# Esquematico.net
KiCad netlist of a schematic drawn in Altium Designer
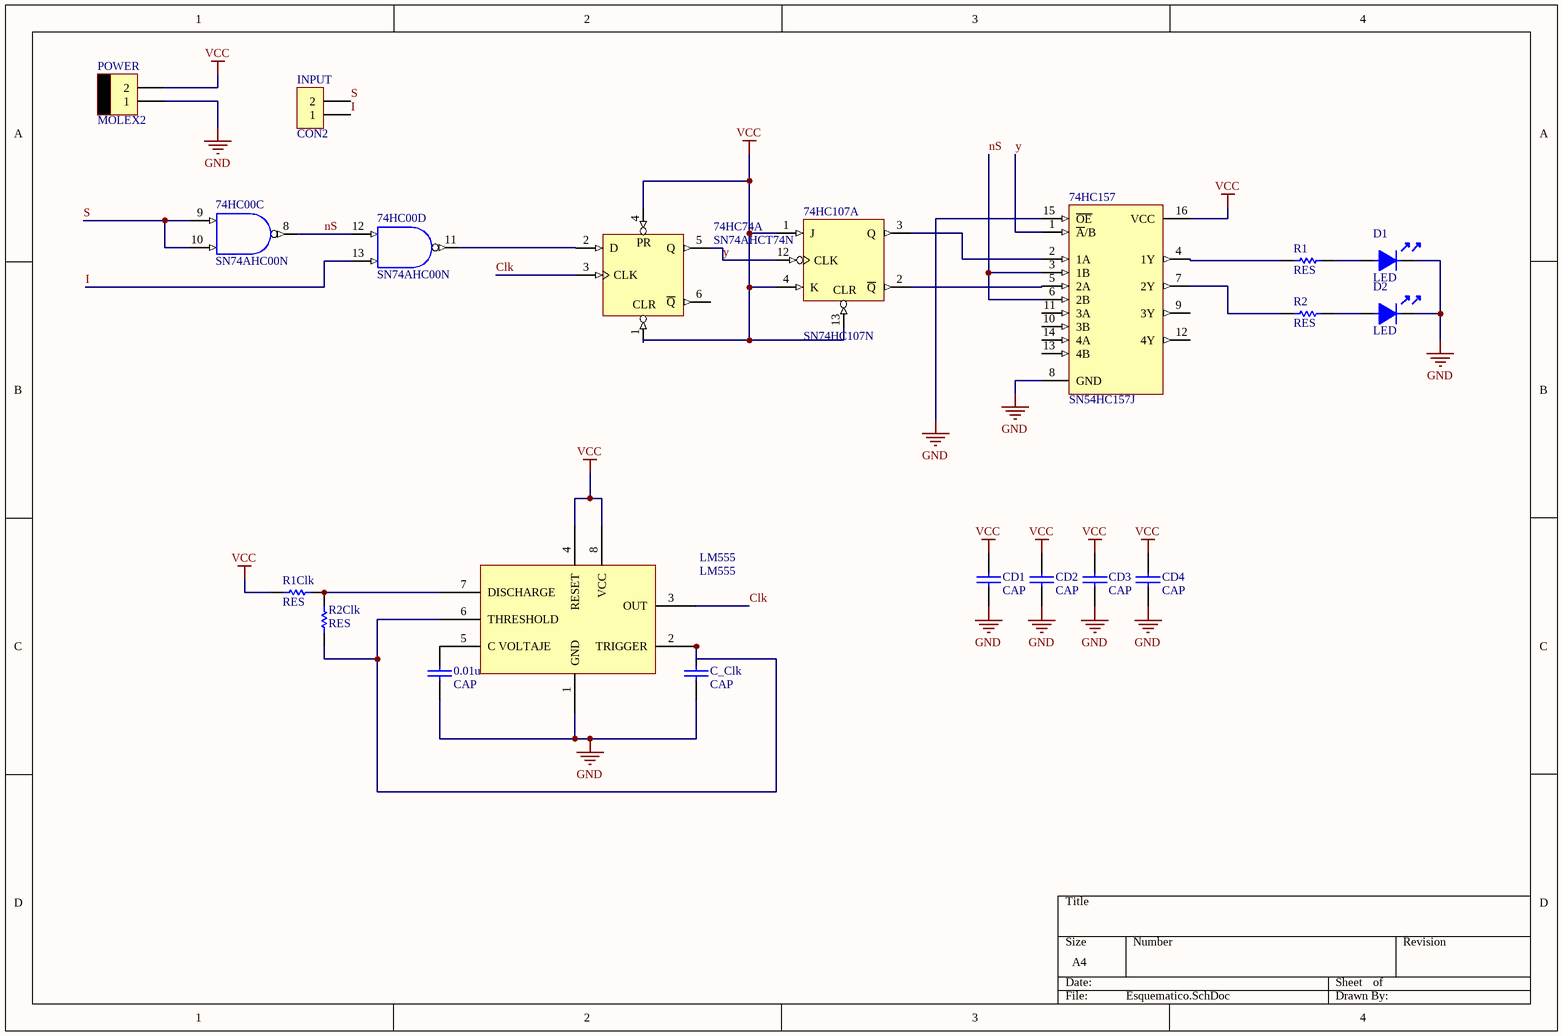
[diagram p0: Esquematico.SchDoc]

(export (version "E")
  (design (tool "Eeschema 10.0.6"))
  (components
    (comp (ref "0.01u") (value "CAP") (footprint "CAP200") (libsource (lib "LIBEBAL") (part "CAP")))
    (comp (ref "74HC00")
      (value "SN74AHC00N")
      (footprint "N014")
      (description "Quadruple 2-Input Positive-NAND Gate")
      (fields (field (name "PUBLISHER") "Altium Limited"))
      (libsource (lib "TI Logic Gate 1") (part "SN74AHC00N"))
    )
    (comp (ref "74HC74")
      (value "SN74AHCT74N")
      (footprint "N014")
      (description "Dual Positive-Edge-Triggered D-Type Flip-Flop with Clear and Preset")
      (fields (field (name "PUBLISHER") "Altium Limited"))
      (libsource (lib "TI Logic Flip-Flop") (part "SN74AHCT74N"))
    )
    (comp (ref "74HC107")
      (value "SN74HC107N")
      (footprint "N014D")
      (description "Dual J-K Negative-Edge-Triggered Flip-Flop with Clear")
      (fields (field (name "PUBLISHER") "Altium Limited"))
      (libsource (lib "TI Logic Flip-Flop") (part "SN74HC107N"))
    )
    (comp (ref "74HC157")
      (value "SN54HC157J")
      (footprint "J016")
      (description "Quadraple 2-Line to 1-Line Data Selector/Multiplexer")
      (fields (field (name "PUBLISHER") "Altium Limited"))
      (libsource (lib "TI Logic Multiplexer") (part "SN54HC157J"))
    )
    (comp (ref "CD1") (value "CAP") (footprint "CAP200") (libsource (lib "LIBEBAL") (part "CAP")))
    (comp (ref "CD2") (value "CAP") (footprint "CAP200") (libsource (lib "LIBEBAL") (part "CAP")))
    (comp (ref "CD3") (value "CAP") (footprint "CAP200") (libsource (lib "LIBEBAL") (part "CAP")))
    (comp (ref "CD4") (value "CAP") (footprint "CAP200") (libsource (lib "LIBEBAL") (part "CAP")))
    (comp (ref "C_Clk") (value "CAP") (footprint "CAP200") (libsource (lib "LIBEBAL") (part "CAP")))
    (comp (ref "D1") (value "LED") (footprint "LED3") (libsource (lib "LIBEBAL") (part "LED")))
    (comp (ref "D2") (value "LED") (footprint "LED3") (libsource (lib "LIBEBAL") (part "LED")))
    (comp (ref "INPUT") (value "CON2") (footprint "SIP2") (libsource (lib "LIBEBAL") (part "CON2")))
    (comp (ref "LM555")
      (value "LM555")
      (footprint "DIP8")
      (description "Timer")
      (libsource (lib "LIBEBAL") (part "LM555"))
    )
    (comp (ref "POWER") (value "MOLEX2") (footprint "MOLEX2") (libsource (lib "LIBEBAL") (part "MOLEX2")))
    (comp (ref "R1") (value "RES") (footprint "RES400") (libsource (lib "LIBEBAL") (part "RES")))
    (comp (ref "R1Clk") (value "RES") (footprint "RES400") (libsource (lib "LIBEBAL") (part "RES")))
    (comp (ref "R2") (value "RES") (footprint "RES400") (libsource (lib "LIBEBAL") (part "RES")))
    (comp (ref "R2Clk") (value "RES") (footprint "RES400") (libsource (lib "LIBEBAL") (part "RES")))
  )
  (nets
    (net (code "1") (name "/Clk") (class "Default")
      (node (ref "74HC74") (pin "3") (pinfunction "CLK_3") (pintype "input"))
      (node (ref "LM555") (pin "3") (pinfunction "OUT_3") (pintype "passive"))
    )
    (net (code "2") (name "/I") (class "Default")
      (node (ref "74HC00") (pin "13") (pinfunction "B_13") (pintype "input"))
      (node (ref "INPUT") (pin "1") (pinfunction "1_1") (pintype "passive"))
    )
    (net (code "3") (name "/S") (class "Default")
      (node (ref "74HC00") (pin "10") (pinfunction "B_10") (pintype "input"))
      (node (ref "74HC00") (pin "9") (pinfunction "A_9") (pintype "input"))
      (node (ref "INPUT") (pin "2") (pinfunction "2_2") (pintype "passive"))
    )
    (net (code "4") (name "/nS") (class "Default")
      (node (ref "74HC00") (pin "12") (pinfunction "A_12") (pintype "input"))
      (node (ref "74HC00") (pin "8") (pinfunction "Y_8") (pintype "output"))
      (node (ref "74HC157") (pin "3") (pinfunction "1B_3") (pintype "input"))
      (node (ref "74HC157") (pin "6") (pinfunction "2B_6") (pintype "input"))
    )
    (net (code "5") (name "/y") (class "Default")
      (node (ref "74HC107") (pin "12") (pinfunction "CLK_12") (pintype "input"))
      (node (ref "74HC157") (pin "1") (pinfunction "~{A}/B_1") (pintype "input"))
      (node (ref "74HC74") (pin "5") (pinfunction "Q_5") (pintype "output"))
    )
    (net (code "6") (name "GND") (class "Default")
      (node (ref "0.01u") (pin "2") (pinfunction "2_2") (pintype "passive"))
      (node (ref "74HC00") (pin "7") (pinfunction "GND_7") (pintype "power_in"))
      (node (ref "74HC107") (pin "7") (pinfunction "GND_7") (pintype "power_in"))
      (node (ref "74HC157") (pin "15") (pinfunction "~{OE}_15") (pintype "input"))
      (node (ref "74HC157") (pin "8") (pinfunction "GND_8") (pintype "power_in"))
      (node (ref "74HC74") (pin "7") (pinfunction "GND_7") (pintype "power_in"))
      (node (ref "CD1") (pin "2") (pinfunction "2_2") (pintype "passive"))
      (node (ref "CD2") (pin "2") (pinfunction "2_2") (pintype "passive"))
      (node (ref "CD3") (pin "2") (pinfunction "2_2") (pintype "passive"))
      (node (ref "CD4") (pin "2") (pinfunction "2_2") (pintype "passive"))
      (node (ref "C_Clk") (pin "2") (pinfunction "2_2") (pintype "passive"))
      (node (ref "D1") (pin "2") (pinfunction "2_2") (pintype "passive"))
      (node (ref "D2") (pin "2") (pinfunction "2_2") (pintype "passive"))
      (node (ref "LM555") (pin "1") (pinfunction "GND_1") (pintype "passive"))
      (node (ref "POWER") (pin "1") (pinfunction "1_1") (pintype "passive"))
    )
    (net (code "7") (name "Net-(74HC00D-Y)") (class "Default")
      (node (ref "74HC00") (pin "11") (pinfunction "Y_11") (pintype "output"))
      (node (ref "74HC74") (pin "2") (pinfunction "D_2") (pintype "input"))
    )
    (net (code "8") (name "Net-(74HC107A-Q)") (class "Default")
      (node (ref "74HC107") (pin "3") (pinfunction "Q_3") (pintype "output"))
      (node (ref "74HC157") (pin "2") (pinfunction "1A_2") (pintype "input"))
    )
    (net (code "9") (name "Net-(74HC107A-~{Q})") (class "Default")
      (node (ref "74HC107") (pin "2") (pinfunction "~{Q}_2") (pintype "output"))
      (node (ref "74HC157") (pin "5") (pinfunction "2A_5") (pintype "input"))
    )
    (net (code "10") (name "Net-(74HC157-1Y)") (class "Default")
      (node (ref "74HC157") (pin "4") (pinfunction "1Y_4") (pintype "output"))
      (node (ref "R1") (pin "1") (pinfunction "1_1") (pintype "passive"))
    )
    (net (code "11") (name "Net-(74HC157-2Y)") (class "Default")
      (node (ref "74HC157") (pin "7") (pinfunction "2Y_7") (pintype "output"))
      (node (ref "R2") (pin "1") (pinfunction "1_1") (pintype "passive"))
    )
    (net (code "12") (name "Net-(D1-Pad1)") (class "Default")
      (node (ref "D1") (pin "1") (pinfunction "1_1") (pintype "passive"))
      (node (ref "R1") (pin "2") (pinfunction "2_2") (pintype "passive"))
    )
    (net (code "13") (name "Net-(D2-Pad1)") (class "Default")
      (node (ref "D2") (pin "1") (pinfunction "1_1") (pintype "passive"))
      (node (ref "R2") (pin "2") (pinfunction "2_2") (pintype "passive"))
    )
    (net (code "14") (name "Net-(LM555-C_VOLTAJE)") (class "Default")
      (node (ref "0.01u") (pin "1") (pinfunction "1_1") (pintype "passive"))
      (node (ref "LM555") (pin "5") (pinfunction "C_VOLTAJE_5") (pintype "passive"))
    )
    (net (code "15") (name "Net-(LM555-DISCHARGE)") (class "Default")
      (node (ref "LM555") (pin "7") (pinfunction "DISCHARGE_7") (pintype "passive"))
      (node (ref "R1Clk") (pin "2") (pinfunction "2_2") (pintype "passive"))
      (node (ref "R2Clk") (pin "2") (pinfunction "2_2") (pintype "passive"))
    )
    (net (code "16") (name "Net-(LM555-THRESHOLD)") (class "Default")
      (node (ref "C_Clk") (pin "1") (pinfunction "1_1") (pintype "passive"))
      (node (ref "LM555") (pin "2") (pinfunction "TRIGGER_2") (pintype "passive"))
      (node (ref "LM555") (pin "6") (pinfunction "THRESHOLD_6") (pintype "passive"))
      (node (ref "R2Clk") (pin "1") (pinfunction "1_1") (pintype "passive"))
    )
    (net (code "17") (name "VCC") (class "Default")
      (node (ref "74HC00") (pin "14") (pinfunction "VCC_14") (pintype "power_in"))
      (node (ref "74HC107") (pin "1") (pinfunction "J_1") (pintype "input"))
      (node (ref "74HC107") (pin "13") (pinfunction "CLR_13") (pintype "input"))
      (node (ref "74HC107") (pin "14") (pinfunction "VCC_14") (pintype "power_in"))
      (node (ref "74HC107") (pin "4") (pinfunction "K_4") (pintype "input"))
      (node (ref "74HC157") (pin "16") (pinfunction "VCC_16") (pintype "power_in"))
      (node (ref "74HC74") (pin "1") (pinfunction "CLR_1") (pintype "input"))
      (node (ref "74HC74") (pin "14") (pinfunction "VCC_14") (pintype "power_in"))
      (node (ref "74HC74") (pin "4") (pinfunction "PR_4") (pintype "input"))
      (node (ref "CD1") (pin "1") (pinfunction "1_1") (pintype "passive"))
      (node (ref "CD2") (pin "1") (pinfunction "1_1") (pintype "passive"))
      (node (ref "CD3") (pin "1") (pinfunction "1_1") (pintype "passive"))
      (node (ref "CD4") (pin "1") (pinfunction "1_1") (pintype "passive"))
      (node (ref "LM555") (pin "4") (pinfunction "RESET_4") (pintype "passive"))
      (node (ref "LM555") (pin "8") (pinfunction "VCC_8") (pintype "passive"))
      (node (ref "POWER") (pin "2") (pinfunction "2_2") (pintype "passive"))
      (node (ref "R1Clk") (pin "1") (pinfunction "1_1") (pintype "passive"))
    )
    (net (code "18") (name "unconnected-(74HC74A-~{Q}-Pad6)") (class "Default")
      (node (ref "74HC74") (pin "6") (pinfunction "~{Q}_6") (pintype "output"))
    )
    (net (code "19") (name "unconnected-(74HC157-3A-Pad11)") (class "Default")
      (node (ref "74HC157") (pin "11") (pinfunction "3A_11") (pintype "input"))
    )
    (net (code "20") (name "unconnected-(74HC157-3B-Pad10)") (class "Default")
      (node (ref "74HC157") (pin "10") (pinfunction "3B_10") (pintype "input"))
    )
    (net (code "21") (name "unconnected-(74HC157-3Y-Pad9)") (class "Default")
      (node (ref "74HC157") (pin "9") (pinfunction "3Y_9") (pintype "output"))
    )
    (net (code "22") (name "unconnected-(74HC157-4A-Pad14)") (class "Default")
      (node (ref "74HC157") (pin "14") (pinfunction "4A_14") (pintype "input"))
    )
    (net (code "23") (name "unconnected-(74HC157-4B-Pad13)") (class "Default")
      (node (ref "74HC157") (pin "13") (pinfunction "4B_13") (pintype "input"))
    )
    (net (code "24") (name "unconnected-(74HC157-4Y-Pad12)") (class "Default")
      (node (ref "74HC157") (pin "12") (pinfunction "4Y_12") (pintype "output"))
    )
  )
)
